# Multi_LT_circuit.net
KiCad netlist of a schematic drawn in Altium Designer
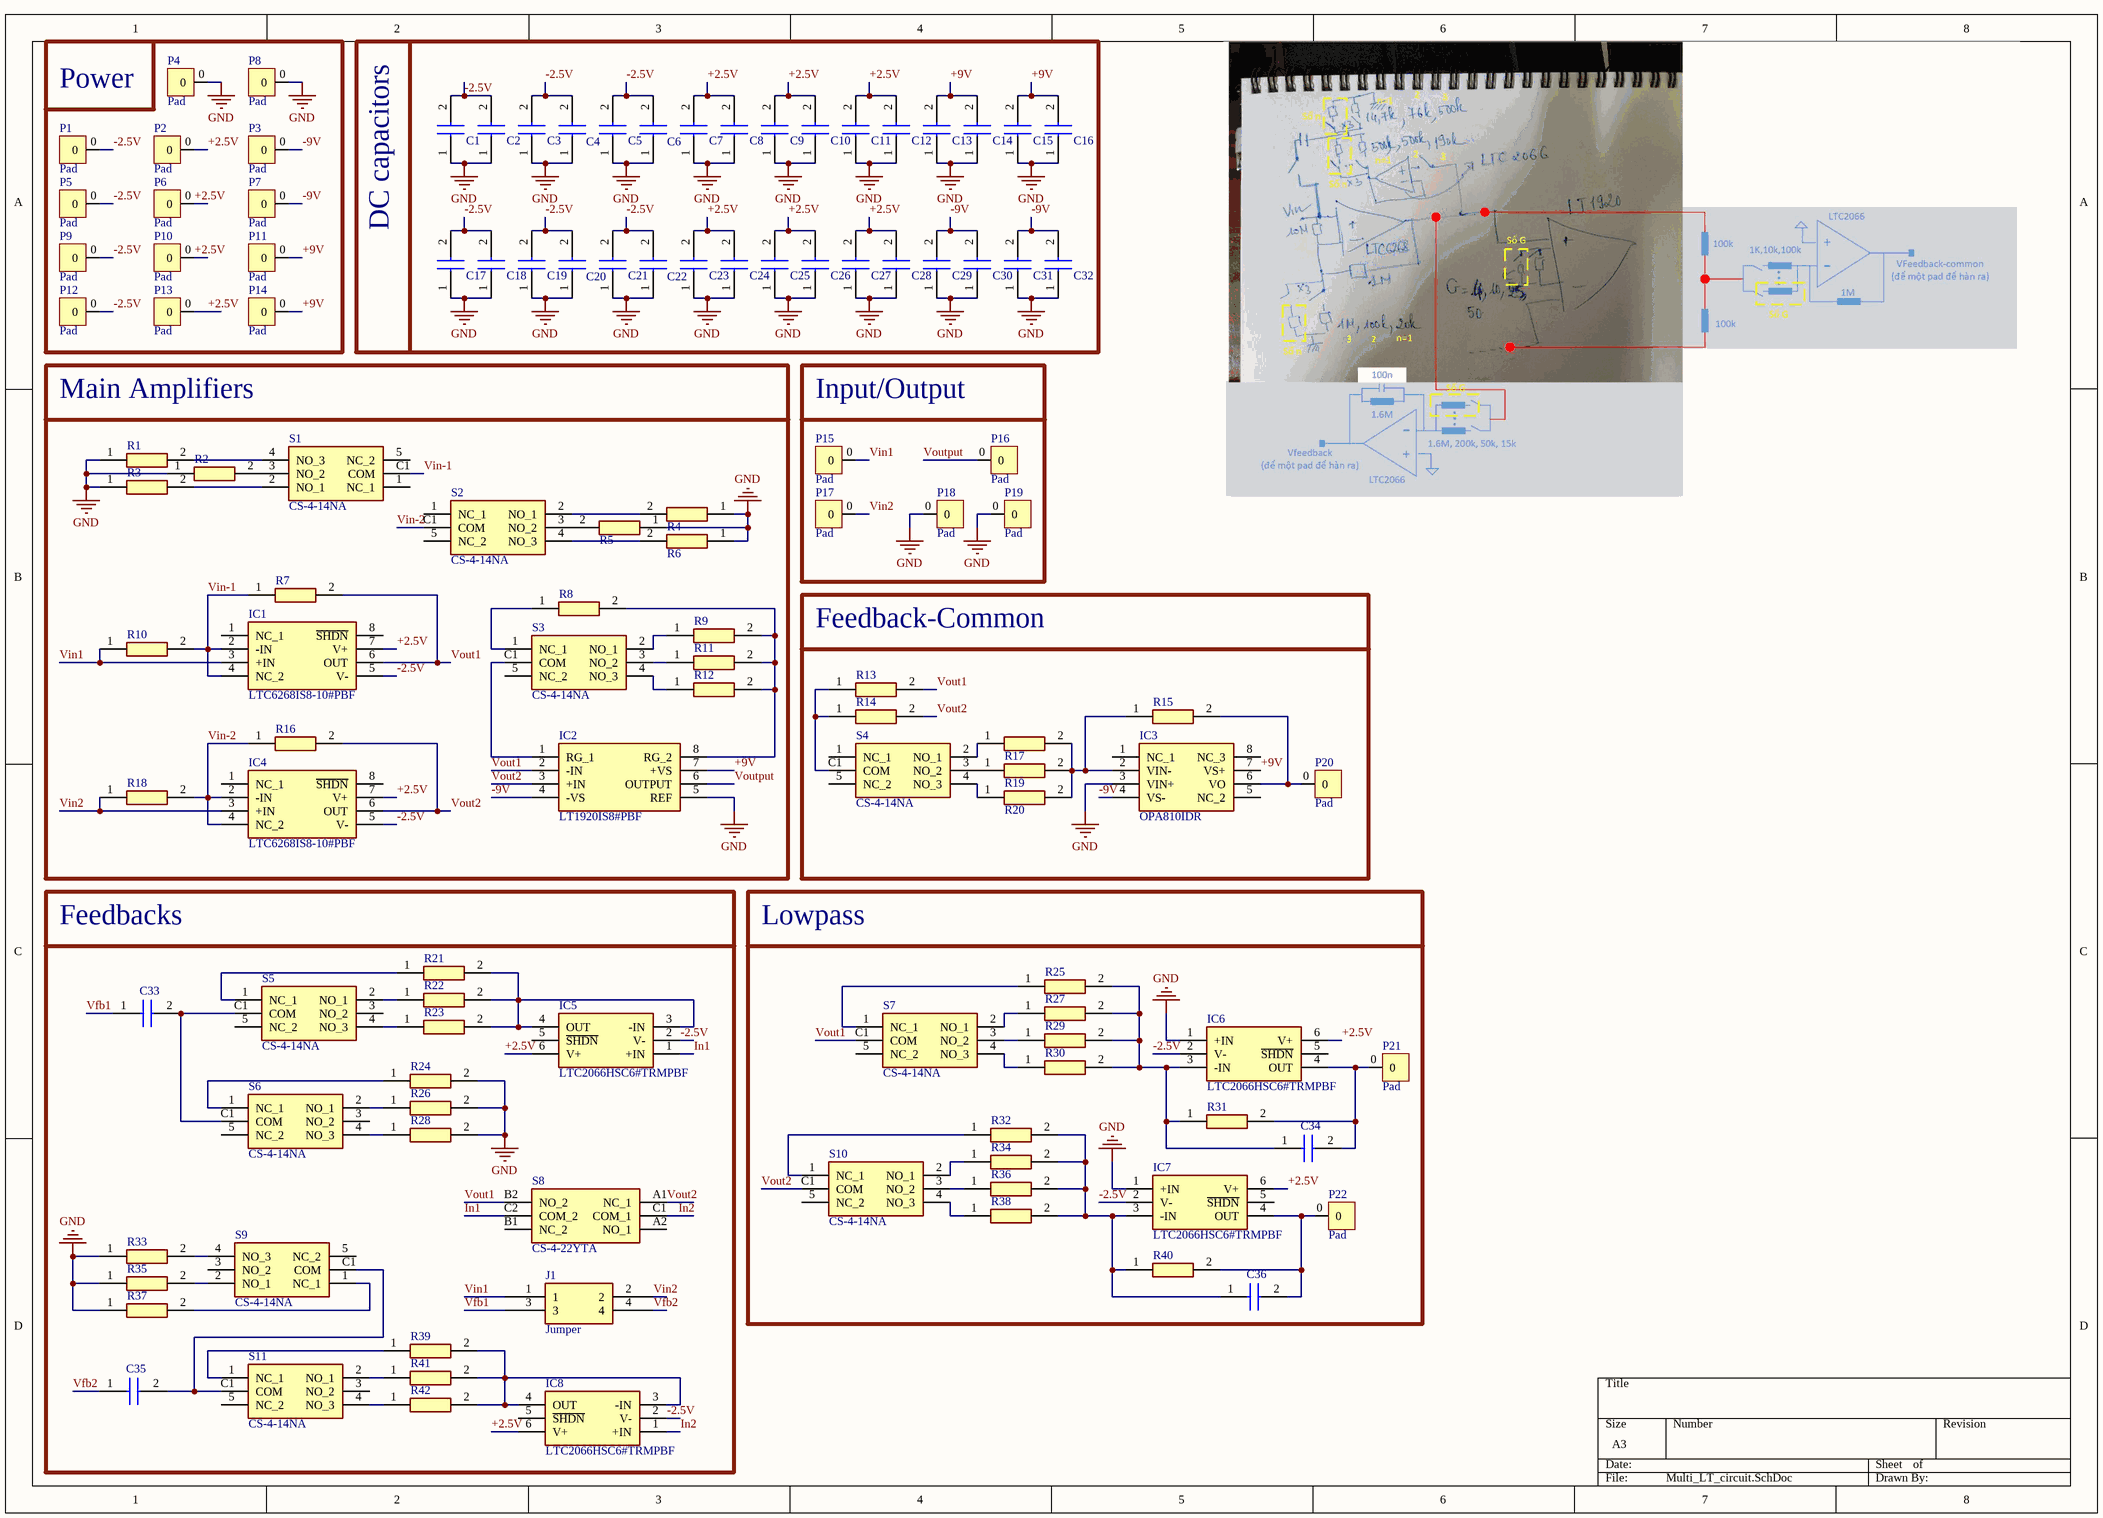
[diagram p0: Multi_LT_circuit.SchDoc]

(export (version "E")
  (design (tool "Eeschema 10.0.6"))
  (components
    (comp (ref "C1")
      (value "GCM21BD70J106KE02K")
      (footprint "SamacSys:CAPC2012X140N")
      (description "Capacitor 10uF")
      (fields (field (name "MOUSER PART NUMBER") "81-GCM21BD70J106KE2K"))
      (libsource (lib "SamacSys") (part "GCM21BD70J106KE02K"))
    )
    (comp (ref "C2")
      (value "GCJ21BR72A104KA01K")
      (footprint "SamacSys:CAPC2012X150N")
      (description "Capacitor 0.1uF")
      (fields (field (name "MOUSER PART NUMBER") "81-GCJ21BR72A104KA01"))
      (libsource (lib "SamacSys") (part "GCJ21BR72A104KA01K"))
    )
    (comp (ref "C3")
      (value "GCM21BD70J106KE02K")
      (footprint "SamacSys:CAPC2012X140N")
      (description "Capacitor 10uF")
      (fields (field (name "MOUSER PART NUMBER") "81-GCM21BD70J106KE2K"))
      (libsource (lib "SamacSys") (part "GCM21BD70J106KE02K"))
    )
    (comp (ref "C4")
      (value "GCJ21BR72A104KA01K")
      (footprint "SamacSys:CAPC2012X150N")
      (description "Capacitor 0.1uF")
      (fields (field (name "MOUSER PART NUMBER") "81-GCJ21BR72A104KA01"))
      (libsource (lib "SamacSys") (part "GCJ21BR72A104KA01K"))
    )
    (comp (ref "C5")
      (value "GCM21BD70J106KE02K")
      (footprint "SamacSys:CAPC2012X140N")
      (description "Capacitor 10uF")
      (fields (field (name "MOUSER PART NUMBER") "81-GCM21BD70J106KE2K"))
      (libsource (lib "SamacSys") (part "GCM21BD70J106KE02K"))
    )
    (comp (ref "C6")
      (value "GCJ21BR72A104KA01K")
      (footprint "SamacSys:CAPC2012X150N")
      (description "Capacitor 0.1uF")
      (fields (field (name "MOUSER PART NUMBER") "81-GCJ21BR72A104KA01"))
      (libsource (lib "SamacSys") (part "GCJ21BR72A104KA01K"))
    )
    (comp (ref "C7")
      (value "GCM21BD70J106KE02K")
      (footprint "SamacSys:CAPC2012X140N")
      (description "Capacitor 10uF")
      (fields (field (name "MOUSER PART NUMBER") "81-GCM21BD70J106KE2K"))
      (libsource (lib "SamacSys") (part "GCM21BD70J106KE02K"))
    )
    (comp (ref "C8")
      (value "GCJ21BR72A104KA01K")
      (footprint "SamacSys:CAPC2012X150N")
      (description "Capacitor 0.1uF")
      (fields (field (name "MOUSER PART NUMBER") "81-GCJ21BR72A104KA01"))
      (libsource (lib "SamacSys") (part "GCJ21BR72A104KA01K"))
    )
    (comp (ref "C9")
      (value "GCM21BD70J106KE02K")
      (footprint "SamacSys:CAPC2012X140N")
      (description "Capacitor 10uF")
      (fields (field (name "MOUSER PART NUMBER") "81-GCM21BD70J106KE2K"))
      (libsource (lib "SamacSys") (part "GCM21BD70J106KE02K"))
    )
    (comp (ref "C10")
      (value "GCJ21BR72A104KA01K")
      (footprint "SamacSys:CAPC2012X150N")
      (description "Capacitor 0.1uF")
      (fields (field (name "MOUSER PART NUMBER") "81-GCJ21BR72A104KA01"))
      (libsource (lib "SamacSys") (part "GCJ21BR72A104KA01K"))
    )
    (comp (ref "C11")
      (value "GCM21BD70J106KE02K")
      (footprint "SamacSys:CAPC2012X140N")
      (description "Capacitor 10uF")
      (fields (field (name "MOUSER PART NUMBER") "81-GCM21BD70J106KE2K"))
      (libsource (lib "SamacSys") (part "GCM21BD70J106KE02K"))
    )
    (comp (ref "C12")
      (value "GCJ21BR72A104KA01K")
      (footprint "SamacSys:CAPC2012X150N")
      (description "Capacitor 0.1uF")
      (fields (field (name "MOUSER PART NUMBER") "81-GCJ21BR72A104KA01"))
      (libsource (lib "SamacSys") (part "GCJ21BR72A104KA01K"))
    )
    (comp (ref "C13")
      (value "GCM21BD70J106KE02K")
      (footprint "SamacSys:CAPC2012X140N")
      (description "Capacitor 10uF")
      (fields (field (name "MOUSER PART NUMBER") "81-GCM21BD70J106KE2K"))
      (libsource (lib "SamacSys") (part "GCM21BD70J106KE02K"))
    )
    (comp (ref "C14")
      (value "GCJ21BR72A104KA01K")
      (footprint "SamacSys:CAPC2012X150N")
      (description "Capacitor 0.1uF")
      (fields (field (name "MOUSER PART NUMBER") "81-GCJ21BR72A104KA01"))
      (libsource (lib "SamacSys") (part "GCJ21BR72A104KA01K"))
    )
    (comp (ref "C15")
      (value "GCM21BD70J106KE02K")
      (footprint "SamacSys:CAPC2012X140N")
      (description "Capacitor 10uF")
      (fields (field (name "MOUSER PART NUMBER") "81-GCM21BD70J106KE2K"))
      (libsource (lib "SamacSys") (part "GCM21BD70J106KE02K"))
    )
    (comp (ref "C16")
      (value "GCJ21BR72A104KA01K")
      (footprint "SamacSys:CAPC2012X150N")
      (description "Capacitor 0.1uF")
      (fields (field (name "MOUSER PART NUMBER") "81-GCJ21BR72A104KA01"))
      (libsource (lib "SamacSys") (part "GCJ21BR72A104KA01K"))
    )
    (comp (ref "C17")
      (value "GCM21BD70J106KE02K")
      (footprint "SamacSys:CAPC2012X140N")
      (description "Capacitor 10uF")
      (fields (field (name "MOUSER PART NUMBER") "81-GCM21BD70J106KE2K"))
      (libsource (lib "SamacSys") (part "GCM21BD70J106KE02K"))
    )
    (comp (ref "C18")
      (value "GCJ21BR72A104KA01K")
      (footprint "SamacSys:CAPC2012X150N")
      (description "Capacitor 0.1uF")
      (fields (field (name "MOUSER PART NUMBER") "81-GCJ21BR72A104KA01"))
      (libsource (lib "SamacSys") (part "GCJ21BR72A104KA01K"))
    )
    (comp (ref "C19")
      (value "GCM21BD70J106KE02K")
      (footprint "SamacSys:CAPC2012X140N")
      (description "Capacitor 10uF")
      (fields (field (name "MOUSER PART NUMBER") "81-GCM21BD70J106KE2K"))
      (libsource (lib "SamacSys") (part "GCM21BD70J106KE02K"))
    )
    (comp (ref "C20")
      (value "GCJ21BR72A104KA01K")
      (footprint "SamacSys:CAPC2012X150N")
      (description "Capacitor 0.1uF")
      (fields (field (name "MOUSER PART NUMBER") "81-GCJ21BR72A104KA01"))
      (libsource (lib "SamacSys") (part "GCJ21BR72A104KA01K"))
    )
    (comp (ref "C21")
      (value "GCM21BD70J106KE02K")
      (footprint "SamacSys:CAPC2012X140N")
      (description "Capacitor 10uF")
      (fields (field (name "MOUSER PART NUMBER") "81-GCM21BD70J106KE2K"))
      (libsource (lib "SamacSys") (part "GCM21BD70J106KE02K"))
    )
    (comp (ref "C22")
      (value "GCJ21BR72A104KA01K")
      (footprint "SamacSys:CAPC2012X150N")
      (description "Capacitor 0.1uF")
      (fields (field (name "MOUSER PART NUMBER") "81-GCJ21BR72A104KA01"))
      (libsource (lib "SamacSys") (part "GCJ21BR72A104KA01K"))
    )
    (comp (ref "C23")
      (value "GCM21BD70J106KE02K")
      (footprint "SamacSys:CAPC2012X140N")
      (description "Capacitor 10uF")
      (fields (field (name "MOUSER PART NUMBER") "81-GCM21BD70J106KE2K"))
      (libsource (lib "SamacSys") (part "GCM21BD70J106KE02K"))
    )
    (comp (ref "C24")
      (value "GCJ21BR72A104KA01K")
      (footprint "SamacSys:CAPC2012X150N")
      (description "Capacitor 0.1uF")
      (fields (field (name "MOUSER PART NUMBER") "81-GCJ21BR72A104KA01"))
      (libsource (lib "SamacSys") (part "GCJ21BR72A104KA01K"))
    )
    (comp (ref "C25")
      (value "GCM21BD70J106KE02K")
      (footprint "SamacSys:CAPC2012X140N")
      (description "Capacitor 10uF")
      (fields (field (name "MOUSER PART NUMBER") "81-GCM21BD70J106KE2K"))
      (libsource (lib "SamacSys") (part "GCM21BD70J106KE02K"))
    )
    (comp (ref "C26")
      (value "GCJ21BR72A104KA01K")
      (footprint "SamacSys:CAPC2012X150N")
      (description "Capacitor 0.1uF")
      (fields (field (name "MOUSER PART NUMBER") "81-GCJ21BR72A104KA01"))
      (libsource (lib "SamacSys") (part "GCJ21BR72A104KA01K"))
    )
    (comp (ref "C27")
      (value "GCM21BD70J106KE02K")
      (footprint "SamacSys:CAPC2012X140N")
      (description "Capacitor 10uF")
      (fields (field (name "MOUSER PART NUMBER") "81-GCM21BD70J106KE2K"))
      (libsource (lib "SamacSys") (part "GCM21BD70J106KE02K"))
    )
    (comp (ref "C28")
      (value "GCJ21BR72A104KA01K")
      (footprint "SamacSys:CAPC2012X150N")
      (description "Capacitor 0.1uF")
      (fields (field (name "MOUSER PART NUMBER") "81-GCJ21BR72A104KA01"))
      (libsource (lib "SamacSys") (part "GCJ21BR72A104KA01K"))
    )
    (comp (ref "C29")
      (value "GCM21BD70J106KE02K")
      (footprint "SamacSys:CAPC2012X140N")
      (description "Capacitor 10uF")
      (fields (field (name "MOUSER PART NUMBER") "81-GCM21BD70J106KE2K"))
      (libsource (lib "SamacSys") (part "GCM21BD70J106KE02K"))
    )
    (comp (ref "C30")
      (value "GCJ21BR72A104KA01K")
      (footprint "SamacSys:CAPC2012X150N")
      (description "Capacitor 0.1uF")
      (fields (field (name "MOUSER PART NUMBER") "81-GCJ21BR72A104KA01"))
      (libsource (lib "SamacSys") (part "GCJ21BR72A104KA01K"))
    )
    (comp (ref "C31")
      (value "GCM21BD70J106KE02K")
      (footprint "SamacSys:CAPC2012X140N")
      (description "Capacitor 10uF")
      (fields (field (name "MOUSER PART NUMBER") "81-GCM21BD70J106KE2K"))
      (libsource (lib "SamacSys") (part "GCM21BD70J106KE02K"))
    )
    (comp (ref "C32")
      (value "GCJ21BR72A104KA01K")
      (footprint "SamacSys:CAPC2012X150N")
      (description "Capacitor 0.1uF")
      (fields (field (name "MOUSER PART NUMBER") "81-GCJ21BR72A104KA01"))
      (libsource (lib "SamacSys") (part "GCJ21BR72A104KA01K"))
    )
    (comp (ref "C33")
      (value "C0805C109B3GACTU")
      (footprint "SamacSys:C0805")
      (description "Capacitor 1pF")
      (libsource (lib "SamacSys") (part "C0805C109B3GACTU"))
    )
    (comp (ref "C34")
      (value "GCJ21BR72A104KA01K")
      (footprint "SamacSys:CAPC2012X150N")
      (description "Capacitor 0.1uF")
      (fields (field (name "MOUSER PART NUMBER") "81-GCJ21BR72A104KA01"))
      (libsource (lib "SamacSys") (part "GCJ21BR72A104KA01K"))
    )
    (comp (ref "C35")
      (value "C0805C109B3GACTU")
      (footprint "SamacSys:C0805")
      (description "Capacitor 1pF")
      (libsource (lib "SamacSys") (part "C0805C109B3GACTU"))
    )
    (comp (ref "C36")
      (value "GCJ21BR72A104KA01K")
      (footprint "SamacSys:CAPC2012X150N")
      (description "Capacitor 0.1uF")
      (fields (field (name "MOUSER PART NUMBER") "81-GCJ21BR72A104KA01"))
      (libsource (lib "SamacSys") (part "GCJ21BR72A104KA01K"))
    )
    (comp (ref "IC1")
      (value "LTC6268IS8-10#PBF")
      (footprint "SamacSys:SOIC127P599X175-8N")
      (description "Integrated Circuit")
      (fields (field (name "MOUSER PART NUMBER") "584-LTC6268IS8-10PBF"))
      (libsource (lib "SamacSys") (part "LTC6268IS8-10#PBF"))
    )
    (comp (ref "IC2")
      (value "LT1920IS8#PBF")
      (footprint "SamacSys:SOIC127P599X175-8N")
      (description "Integrated Circuit")
      (fields (field (name "MOUSER PART NUMBER") "584-LT1920IS8#PBF"))
      (libsource (lib "SamacSys") (part "LT1920IS8#PBF"))
    )
    (comp (ref "IC3")
      (value "OPA810IDR")
      (footprint "SamacSys:SOIC127P600X175-8N")
      (description "Integrated Circuit")
      (fields (field (name "MOUSER PART NUMBER") "595-OPA810IDR"))
      (libsource (lib "SamacSys") (part "OPA810IDR"))
    )
    (comp (ref "IC4")
      (value "LTC6268IS8-10#PBF")
      (footprint "SamacSys:SOIC127P599X175-8N")
      (description "Integrated Circuit")
      (fields (field (name "MOUSER PART NUMBER") "584-LTC6268IS8-10PBF"))
      (libsource (lib "SamacSys") (part "LTC6268IS8-10#PBF"))
    )
    (comp (ref "IC5")
      (value "LTC2066HSC6#TRMPBF")
      (footprint "SamacSys:SOT65P210X100-6N")
      (description "Integrated Circuit")
      (fields (field (name "MOUSER PART NUMBER") "584-LTC2066HSC6TRMPB"))
      (libsource (lib "") (part "LTC2066HSC6#TRMPBF_1"))
    )
    (comp (ref "IC6")
      (value "LTC2066HSC6#TRMPBF")
      (footprint "SamacSys:SOT65P210X100-6N")
      (description "Integrated Circuit")
      (fields (field (name "MOUSER PART NUMBER") "584-LTC2066HSC6TRMPB"))
      (libsource (lib "SamacSys") (part "LTC2066HSC6#TRMPBF"))
    )
    (comp (ref "IC7")
      (value "LTC2066HSC6#TRMPBF")
      (footprint "SamacSys:SOT65P210X100-6N")
      (description "Integrated Circuit")
      (fields (field (name "MOUSER PART NUMBER") "584-LTC2066HSC6TRMPB"))
      (libsource (lib "SamacSys") (part "LTC2066HSC6#TRMPBF"))
    )
    (comp (ref "IC8")
      (value "LTC2066HSC6#TRMPBF")
      (footprint "SamacSys:SOT65P210X100-6N")
      (description "Integrated Circuit")
      (fields (field (name "MOUSER PART NUMBER") "584-LTC2066HSC6TRMPB"))
      (libsource (lib "") (part "LTC2066HSC6#TRMPBF_1"))
    )
    (comp (ref "J1") (value "Jumper") (footprint "Jumper 2x2") (libsource (lib "SamacSys") (part "Jumper")))
    (comp (ref "P1") (value "Pad") (footprint "Pad") (libsource (lib "") (part "Pad_1")))
    (comp (ref "P2") (value "Pad") (footprint "Pad") (libsource (lib "") (part "Pad_1")))
    (comp (ref "P3") (value "Pad") (footprint "Pad") (libsource (lib "") (part "Pad_1")))
    (comp (ref "P4") (value "Pad") (footprint "Pad") (libsource (lib "") (part "Pad_1")))
    (comp (ref "P5") (value "Pad") (footprint "Pad") (libsource (lib "") (part "Pad_1")))
    (comp (ref "P6") (value "Pad") (footprint "Pad") (libsource (lib "") (part "Pad_1")))
    (comp (ref "P7") (value "Pad") (footprint "Pad") (libsource (lib "") (part "Pad_1")))
    (comp (ref "P8") (value "Pad") (footprint "Pad") (libsource (lib "") (part "Pad_1")))
    (comp (ref "P9") (value "Pad") (footprint "Pad") (libsource (lib "") (part "Pad_1")))
    (comp (ref "P10") (value "Pad") (footprint "Pad") (libsource (lib "") (part "Pad_1")))
    (comp (ref "P11") (value "Pad") (footprint "Pad") (libsource (lib "") (part "Pad_1")))
    (comp (ref "P12") (value "Pad") (footprint "Pad") (libsource (lib "") (part "Pad_1")))
    (comp (ref "P13") (value "Pad") (footprint "Pad") (libsource (lib "") (part "Pad_1")))
    (comp (ref "P14") (value "Pad") (footprint "Pad") (libsource (lib "") (part "Pad_1")))
    (comp (ref "P15") (value "Pad") (footprint "Pad") (libsource (lib "") (part "Pad_1")))
    (comp (ref "P16") (value "Pad") (footprint "Pad") (libsource (lib "SamacSys") (part "Pad")))
    (comp (ref "P17") (value "Pad") (footprint "Pad") (libsource (lib "") (part "Pad_1")))
    (comp (ref "P18") (value "Pad") (footprint "Pad") (libsource (lib "SamacSys") (part "Pad")))
    (comp (ref "P19") (value "Pad") (footprint "Pad") (libsource (lib "SamacSys") (part "Pad")))
    (comp (ref "P20") (value "Pad") (footprint "Pad") (libsource (lib "SamacSys") (part "Pad")))
    (comp (ref "P21") (value "Pad") (footprint "Pad") (libsource (lib "SamacSys") (part "Pad")))
    (comp (ref "P22") (value "Pad") (footprint "Pad") (libsource (lib "SamacSys") (part "Pad")))
    (comp (ref "R1")
      (value "CRG0805F20K")
      (footprint "SamacSys:RESC2012X65N")
      (description "Resistor 20k")
      (fields (field (name "MOUSER PART NUMBER") "279-CRG0805F20K"))
      (libsource (lib "") (part "CRG0805F20K_1"))
    )
    (comp (ref "R2")
      (value "CRG0805F100K")
      (footprint "SamacSys:RESC2012X65N")
      (description "Resistor 100k")
      (fields (field (name "MOUSER PART NUMBER") "279-CRG0805F100K"))
      (libsource (lib "SamacSys") (part "CRG0805F100K"))
    )
    (comp (ref "R3")
      (value "CRGH0805F1M0")
      (footprint "SamacSys:RESC2013X65N")
      (description "Resistor 1M")
      (fields (field (name "MOUSER PART NUMBER") "279-CRGH0805F1M0"))
      (libsource (lib "SamacSys") (part "CRGH0805F1M0"))
    )
    (comp (ref "R4")
      (value "CRG0805F20K")
      (footprint "SamacSys:RESC2012X65N")
      (description "Resistor 20k")
      (fields (field (name "MOUSER PART NUMBER") "279-CRG0805F20K"))
      (libsource (lib "SamacSys") (part "CRG0805F20K"))
    )
    (comp (ref "R5")
      (value "CRG0805F100K")
      (footprint "SamacSys:RESC2012X65N")
      (description "Resistor 100k")
      (fields (field (name "MOUSER PART NUMBER") "279-CRG0805F100K"))
      (libsource (lib "") (part "CRG0805F100K_1"))
    )
    (comp (ref "R6")
      (value "CRGH0805F1M0")
      (footprint "SamacSys:RESC2013X65N")
      (description "Resistor 1M")
      (fields (field (name "MOUSER PART NUMBER") "279-CRGH0805F1M0"))
      (libsource (lib "") (part "CRGH0805F1M0_1"))
    )
    (comp (ref "R7")
      (value "CRGH0805F1M0")
      (footprint "SamacSys:RESC2013X65N")
      (description "Resistor 1M")
      (fields (field (name "MOUSER PART NUMBER") "279-CRGH0805F1M0"))
      (libsource (lib "SamacSys") (part "CRGH0805F1M0"))
    )
    (comp (ref "R8")
      (value "CRGH0805F1K0")
      (footprint "SamacSys:RESC2013X65N")
      (description "Resistor 1k")
      (fields (field (name "MOUSER PART NUMBER") "279-CRGH0805F1K0"))
      (libsource (lib "SamacSys") (part "CRGH0805F1K0"))
    )
    (comp (ref "R9")
      (value "CRCW08052K05FKEA")
      (footprint "SamacSys:RESC2012X50N")
      (description "Resistor 2.05k")
      (fields (field (name "MOUSER PART NUMBER") "71-CRCW0805-2.05K-E3"))
      (libsource (lib "SamacSys") (part "CRCW08052K05FKEA"))
    )
    (comp (ref "R10")
      (value "CRGH0805J10M")
      (footprint "SamacSys:RESC2013X65N")
      (description "Resistor 10M")
      (fields (field (name "MOUSER PART NUMBER") "279-CRGH0805J10M"))
      (libsource (lib "SamacSys") (part "CRGH0805J10M"))
    )
    (comp (ref "R11")
      (value "CRCW08055K49FKEAHP")
      (footprint "SamacSys:RESC2012X60N")
      (description "Resistor 5.49k")
      (libsource (lib "SamacSys") (part "CRCW08055K49FKEAHP"))
    )
    (comp (ref "R12")
      (value "CRCW080516K5FKEA")
      (footprint "SamacSys:RESC2012X50N")
      (description "Resistor 16.5k")
      (fields (field (name "MOUSER PART NUMBER") "71-CRCW0805-16.5K-E3"))
      (libsource (lib "SamacSys") (part "CRCW080516K5FKEA"))
    )
    (comp (ref "R13")
      (value "CRG0805F100K")
      (footprint "SamacSys:RESC2012X65N")
      (description "Resistor 100k")
      (fields (field (name "MOUSER PART NUMBER") "279-CRG0805F100K"))
      (libsource (lib "SamacSys") (part "CRG0805F100K"))
    )
    (comp (ref "R14")
      (value "CRG0805F100K")
      (footprint "SamacSys:RESC2012X65N")
      (description "Resistor 100k")
      (fields (field (name "MOUSER PART NUMBER") "279-CRG0805F100K"))
      (libsource (lib "SamacSys") (part "CRG0805F100K"))
    )
    (comp (ref "R15")
      (value "CRGH0805F1M0")
      (footprint "SamacSys:RESC2013X65N")
      (description "Resistor 1M")
      (fields (field (name "MOUSER PART NUMBER") "279-CRGH0805F1M0"))
      (libsource (lib "SamacSys") (part "CRGH0805F1M0"))
    )
    (comp (ref "R16")
      (value "CRGH0805F1M0")
      (footprint "SamacSys:RESC2013X65N")
      (description "Resistor 1M")
      (fields (field (name "MOUSER PART NUMBER") "279-CRGH0805F1M0"))
      (libsource (lib "SamacSys") (part "CRGH0805F1M0"))
    )
    (comp (ref "R17")
      (value "CRG0805F100K")
      (footprint "SamacSys:RESC2012X65N")
      (description "Resistor 100k")
      (fields (field (name "MOUSER PART NUMBER") "279-CRG0805F100K"))
      (libsource (lib "SamacSys") (part "CRG0805F100K"))
    )
    (comp (ref "R18")
      (value "CRGH0805J10M")
      (footprint "SamacSys:RESC2013X65N")
      (description "Resistor 10M")
      (fields (field (name "MOUSER PART NUMBER") "279-CRGH0805J10M"))
      (libsource (lib "SamacSys") (part "CRGH0805J10M"))
    )
    (comp (ref "R19")
      (value "CRGH0805F10K")
      (footprint "SamacSys:RESC2013X65N")
      (description "Resistor 10k")
      (fields (field (name "MOUSER PART NUMBER") "279-CRGH0805F10K"))
      (libsource (lib "SamacSys") (part "CRGH0805F10K"))
    )
    (comp (ref "R20")
      (value "CRGH0805F1K0")
      (footprint "SamacSys:RESC2013X65N")
      (description "Resistor 1k")
      (fields (field (name "MOUSER PART NUMBER") "279-CRGH0805F1K0"))
      (libsource (lib "SamacSys") (part "CRGH0805F1K0"))
    )
    (comp (ref "R21")
      (value "CPF0805B499KE1")
      (footprint "SamacSys:RESC2012X65N")
      (description "Resistor 499k")
      (fields (field (name "MOUSER PART NUMBER") "279-CPF0805B499KE1"))
      (libsource (lib "SamacSys") (part "CPF0805B499KE1"))
    )
    (comp (ref "R22")
      (value "CPF0805B499KE1")
      (footprint "SamacSys:RESC2012X65N")
      (description "Resistor 499k")
      (fields (field (name "MOUSER PART NUMBER") "279-CPF0805B499KE1"))
      (libsource (lib "SamacSys") (part "CPF0805B499KE1"))
    )
    (comp (ref "R23")
      (value "CRGH0805F191K")
      (footprint "SamacSys:RESC2013X65N")
      (description "Resistor 191k")
      (fields (field (name "MOUSER PART NUMBER") "279-CRGH0805F191K"))
      (libsource (lib "SamacSys") (part "CRGH0805F191K"))
    )
    (comp (ref "R24")
      (value "CPF0805B499KE1")
      (footprint "SamacSys:RESC2012X65N")
      (description "Resistor 499k")
      (fields (field (name "MOUSER PART NUMBER") "279-CPF0805B499KE1"))
      (libsource (lib "SamacSys") (part "CPF0805B499KE1"))
    )
    (comp (ref "R25")
      (value "CPF0805B1M6E1")
      (footprint "SamacSys:RESC2012X65N")
      (description "Resistor 1.6M")
      (fields (field (name "MOUSER PART NUMBER") "279-CPF0805B1M6E1"))
      (libsource (lib "SamacSys") (part "CPF0805B1M6E1"))
    )
    (comp (ref "R26")
      (value "ERJ-6ENF7682V")
      (footprint "SamacSys:ERJ6ENF1000V")
      (description "Resistor 76.8k")
      (fields (field (name "MOUSER PART NUMBER") "667-ERJ-6ENF7682V"))
      (libsource (lib "SamacSys") (part "ERJ-6ENF7682V"))
    )
    (comp (ref "R27")
      (value "CPF-A-0805B200KE")
      (footprint "SamacSys:RESC2012X65N")
      (description "Resistor 200k")
      (fields (field (name "MOUSER PART NUMBER") "279-CPF-A-0805B200KE"))
      (libsource (lib "SamacSys") (part "CPF-A-0805B200KE"))
    )
    (comp (ref "R28")
      (value "CRCW080514K7FKEA")
      (footprint "SamacSys:RESC2012X50N")
      (description "Resistor 14.7k")
      (fields (field (name "MOUSER PART NUMBER") "71-CRCW0805-14.7K-E3"))
      (libsource (lib "SamacSys") (part "CRCW080514K7FKEA"))
    )
    (comp (ref "R29")
      (value "CPF-A-0805B49K9E1")
      (footprint "SamacSys:RESC2012X65N")
      (description "Resistor 49.9k")
      (fields (field (name "MOUSER PART NUMBER") "279-CPF-A0805B49K9E1"))
      (libsource (lib "SamacSys") (part "CPF-A-0805B49K9E1"))
    )
    (comp (ref "R30")
      (value "CRGH0805F15K")
      (footprint "SamacSys:RESC2013X65N")
      (description "Resistor 15k")
      (fields (field (name "MOUSER PART NUMBER") "279-CRGH0805F15K"))
      (libsource (lib "SamacSys") (part "CRGH0805F15K"))
    )
    (comp (ref "R31")
      (value "CPF0805B1M6E1")
      (footprint "SamacSys:RESC2012X65N")
      (description "Resistor 1.6M")
      (fields (field (name "MOUSER PART NUMBER") "279-CPF0805B1M6E1"))
      (libsource (lib "SamacSys") (part "CPF0805B1M6E1"))
    )
    (comp (ref "R32")
      (value "CPF0805B1M6E1")
      (footprint "SamacSys:RESC2012X65N")
      (description "Resistor 1.6M")
      (fields (field (name "MOUSER PART NUMBER") "279-CPF0805B1M6E1"))
      (libsource (lib "SamacSys") (part "CPF0805B1M6E1"))
    )
    (comp (ref "R33")
      (value "CRCW080514K7FKEA")
      (footprint "SamacSys:RESC2012X50N")
      (description "Resistor 14.7k")
      (fields (field (name "MOUSER PART NUMBER") "71-CRCW0805-14.7K-E3"))
      (libsource (lib "SamacSys") (part "CRCW080514K7FKEA"))
    )
    (comp (ref "R34")
      (value "CPF-A-0805B200KE")
      (footprint "SamacSys:RESC2012X65N")
      (description "Resistor 200k")
      (fields (field (name "MOUSER PART NUMBER") "279-CPF-A-0805B200KE"))
      (libsource (lib "SamacSys") (part "CPF-A-0805B200KE"))
    )
    (comp (ref "R35")
      (value "ERJ-6ENF7682V")
      (footprint "SamacSys:ERJ6ENF1000V")
      (description "Resistor 76.8k")
      (fields (field (name "MOUSER PART NUMBER") "667-ERJ-6ENF7682V"))
      (libsource (lib "SamacSys") (part "ERJ-6ENF7682V"))
    )
    (comp (ref "R36")
      (value "CPF-A-0805B49K9E1")
      (footprint "SamacSys:RESC2012X65N")
      (description "Resistor 49.9k")
      (fields (field (name "MOUSER PART NUMBER") "279-CPF-A0805B49K9E1"))
      (libsource (lib "SamacSys") (part "CPF-A-0805B49K9E1"))
    )
    (comp (ref "R37")
      (value "CPF0805B499KE1")
      (footprint "SamacSys:RESC2012X65N")
      (description "Resistor 499k")
      (fields (field (name "MOUSER PART NUMBER") "279-CPF0805B499KE1"))
      (libsource (lib "SamacSys") (part "CPF0805B499KE1"))
    )
    (comp (ref "R38")
      (value "CRGH0805F15K")
      (footprint "SamacSys:RESC2013X65N")
      (description "Resistor 15k")
      (fields (field (name "MOUSER PART NUMBER") "279-CRGH0805F15K"))
      (libsource (lib "SamacSys") (part "CRGH0805F15K"))
    )
    (comp (ref "R39")
      (value "CPF0805B499KE1")
      (footprint "SamacSys:RESC2012X65N")
      (description "Resistor 499k")
      (fields (field (name "MOUSER PART NUMBER") "279-CPF0805B499KE1"))
      (libsource (lib "SamacSys") (part "CPF0805B499KE1"))
    )
    (comp (ref "R40")
      (value "CPF0805B1M6E1")
      (footprint "SamacSys:RESC2012X65N")
      (description "Resistor 1.6M")
      (fields (field (name "MOUSER PART NUMBER") "279-CPF0805B1M6E1"))
      (libsource (lib "SamacSys") (part "CPF0805B1M6E1"))
    )
    (comp (ref "R41")
      (value "CPF0805B499KE1")
      (footprint "SamacSys:RESC2012X65N")
      (description "Resistor 499k")
      (fields (field (name "MOUSER PART NUMBER") "279-CPF0805B499KE1"))
      (libsource (lib "SamacSys") (part "CPF0805B499KE1"))
    )
    (comp (ref "R42")
      (value "CRGH0805F191K")
      (footprint "SamacSys:RESC2013X65N")
      (description "Resistor 191k")
      (fields (field (name "MOUSER PART NUMBER") "279-CRGH0805F191K"))
      (libsource (lib "SamacSys") (part "CRGH0805F191K"))
    )
    (comp (ref "S1")
      (value "CS-4-14NA")
      (footprint "SamacSys:CS414NA")
      (description "Switch")
      (fields (field (name "MOUSER PART NUMBER") "229-CS-4-14NA"))
      (libsource (lib "") (part "CS-4-14NA_1"))
    )
    (comp (ref "S2")
      (value "CS-4-14NA")
      (footprint "SamacSys:CS414NA")
      (description "Switch")
      (fields (field (name "MOUSER PART NUMBER") "229-CS-4-14NA"))
      (libsource (lib "SamacSys") (part "CS-4-14NA"))
    )
    (comp (ref "S3")
      (value "CS-4-14NA")
      (footprint "SamacSys:CS414NA")
      (description "Switch")
      (fields (field (name "MOUSER PART NUMBER") "229-CS-4-14NA"))
      (libsource (lib "SamacSys") (part "CS-4-14NA"))
    )
    (comp (ref "S4")
      (value "CS-4-14NA")
      (footprint "SamacSys:CS414NA")
      (description "Switch")
      (fields (field (name "MOUSER PART NUMBER") "229-CS-4-14NA"))
      (libsource (lib "SamacSys") (part "CS-4-14NA"))
    )
    (comp (ref "S5")
      (value "CS-4-14NA")
      (footprint "SamacSys:CS414NA")
      (description "Switch")
      (fields (field (name "MOUSER PART NUMBER") "229-CS-4-14NA"))
      (libsource (lib "SamacSys") (part "CS-4-14NA"))
    )
    (comp (ref "S6")
      (value "CS-4-14NA")
      (footprint "SamacSys:CS414NA")
      (description "Switch")
      (fields (field (name "MOUSER PART NUMBER") "229-CS-4-14NA"))
      (libsource (lib "SamacSys") (part "CS-4-14NA"))
    )
    (comp (ref "S7")
      (value "CS-4-14NA")
      (footprint "SamacSys:CS414NA")
      (description "Switch")
      (fields (field (name "MOUSER PART NUMBER") "229-CS-4-14NA"))
      (libsource (lib "SamacSys") (part "CS-4-14NA"))
    )
    (comp (ref "S8")
      (value "CS-4-22YTA")
      (footprint "SamacSys:CS422YTA")
      (description "Switch")
      (fields (field (name "MOUSER PART NUMBER") "229-CS-4-22YTA"))
      (libsource (lib "SamacSys") (part "CS-4-22YTA"))
    )
    (comp (ref "S9")
      (value "CS-4-14NA")
      (footprint "SamacSys:CS414NA")
      (description "Switch")
      (fields (field (name "MOUSER PART NUMBER") "229-CS-4-14NA"))
      (libsource (lib "") (part "CS-4-14NA_1"))
    )
    (comp (ref "S10")
      (value "CS-4-14NA")
      (footprint "SamacSys:CS414NA")
      (description "Switch")
      (fields (field (name "MOUSER PART NUMBER") "229-CS-4-14NA"))
      (libsource (lib "SamacSys") (part "CS-4-14NA"))
    )
    (comp (ref "S11")
      (value "CS-4-14NA")
      (footprint "SamacSys:CS414NA")
      (description "Switch")
      (fields (field (name "MOUSER PART NUMBER") "229-CS-4-14NA"))
      (libsource (lib "SamacSys") (part "CS-4-14NA"))
    )
  )
  (nets
    (net (code "1") (name "/+2.5V") (class "Default")
      (node (ref "C10") (pin "2") (pinfunction "2_2") (pintype "passive"))
      (node (ref "C11") (pin "2") (pinfunction "2_2") (pintype "passive"))
      (node (ref "C12") (pin "2") (pinfunction "2_2") (pintype "passive"))
      (node (ref "C23") (pin "2") (pinfunction "2_2") (pintype "passive"))
      (node (ref "C24") (pin "2") (pinfunction "2_2") (pintype "passive"))
      (node (ref "C25") (pin "2") (pinfunction "2_2") (pintype "passive"))
      (node (ref "C26") (pin "2") (pinfunction "2_2") (pintype "passive"))
      (node (ref "C27") (pin "2") (pinfunction "2_2") (pintype "passive"))
      (node (ref "C28") (pin "2") (pinfunction "2_2") (pintype "passive"))
      (node (ref "C7") (pin "2") (pinfunction "2_2") (pintype "passive"))
      (node (ref "C8") (pin "2") (pinfunction "2_2") (pintype "passive"))
      (node (ref "C9") (pin "2") (pinfunction "2_2") (pintype "passive"))
      (node (ref "IC1") (pin "7") (pinfunction "V+_7") (pintype "passive"))
      (node (ref "IC4") (pin "7") (pinfunction "V+_7") (pintype "passive"))
      (node (ref "IC5") (pin "6") (pinfunction "V+_6") (pintype "passive"))
      (node (ref "IC6") (pin "6") (pinfunction "V+_6") (pintype "passive"))
      (node (ref "IC7") (pin "6") (pinfunction "V+_6") (pintype "passive"))
      (node (ref "IC8") (pin "6") (pinfunction "V+_6") (pintype "passive"))
      (node (ref "P10") (pin "0") (pinfunction "0_0") (pintype "passive"))
      (node (ref "P13") (pin "0") (pinfunction "0_0") (pintype "passive"))
      (node (ref "P2") (pin "0") (pinfunction "0_0") (pintype "passive"))
      (node (ref "P6") (pin "0") (pinfunction "0_0") (pintype "passive"))
    )
    (net (code "2") (name "/+9V") (class "Default")
      (node (ref "C13") (pin "2") (pinfunction "2_2") (pintype "passive"))
      (node (ref "C14") (pin "2") (pinfunction "2_2") (pintype "passive"))
      (node (ref "C15") (pin "2") (pinfunction "2_2") (pintype "passive"))
      (node (ref "C16") (pin "2") (pinfunction "2_2") (pintype "passive"))
      (node (ref "IC2") (pin "7") (pinfunction "+VS_7") (pintype "passive"))
      (node (ref "IC3") (pin "7") (pinfunction "VS+_7") (pintype "passive"))
      (node (ref "P11") (pin "0") (pinfunction "0_0") (pintype "passive"))
      (node (ref "P14") (pin "0") (pinfunction "0_0") (pintype "passive"))
    )
    (net (code "3") (name "/-2.5V") (class "Default")
      (node (ref "C1") (pin "2") (pinfunction "2_2") (pintype "passive"))
      (node (ref "C17") (pin "2") (pinfunction "2_2") (pintype "passive"))
      (node (ref "C18") (pin "2") (pinfunction "2_2") (pintype "passive"))
      (node (ref "C19") (pin "2") (pinfunction "2_2") (pintype "passive"))
      (node (ref "C2") (pin "2") (pinfunction "2_2") (pintype "passive"))
      (node (ref "C20") (pin "2") (pinfunction "2_2") (pintype "passive"))
      (node (ref "C21") (pin "2") (pinfunction "2_2") (pintype "passive"))
      (node (ref "C22") (pin "2") (pinfunction "2_2") (pintype "passive"))
      (node (ref "C3") (pin "2") (pinfunction "2_2") (pintype "passive"))
      (node (ref "C4") (pin "2") (pinfunction "2_2") (pintype "passive"))
      (node (ref "C5") (pin "2") (pinfunction "2_2") (pintype "passive"))
      (node (ref "C6") (pin "2") (pinfunction "2_2") (pintype "passive"))
      (node (ref "IC1") (pin "5") (pinfunction "V-_5") (pintype "passive"))
      (node (ref "IC4") (pin "5") (pinfunction "V-_5") (pintype "passive"))
      (node (ref "IC5") (pin "2") (pinfunction "V-_2") (pintype "passive"))
      (node (ref "IC6") (pin "2") (pinfunction "V-_2") (pintype "passive"))
      (node (ref "IC7") (pin "2") (pinfunction "V-_2") (pintype "passive"))
      (node (ref "IC8") (pin "2") (pinfunction "V-_2") (pintype "passive"))
      (node (ref "P1") (pin "0") (pinfunction "0_0") (pintype "passive"))
      (node (ref "P12") (pin "0") (pinfunction "0_0") (pintype "passive"))
      (node (ref "P5") (pin "0") (pinfunction "0_0") (pintype "passive"))
      (node (ref "P9") (pin "0") (pinfunction "0_0") (pintype "passive"))
    )
    (net (code "4") (name "/-9V") (class "Default")
      (node (ref "C29") (pin "2") (pinfunction "2_2") (pintype "passive"))
      (node (ref "C30") (pin "2") (pinfunction "2_2") (pintype "passive"))
      (node (ref "C31") (pin "2") (pinfunction "2_2") (pintype "passive"))
      (node (ref "C32") (pin "2") (pinfunction "2_2") (pintype "passive"))
      (node (ref "IC2") (pin "4") (pinfunction "-VS_4") (pintype "passive"))
      (node (ref "IC3") (pin "4") (pinfunction "VS-_4") (pintype "passive"))
      (node (ref "P3") (pin "0") (pinfunction "0_0") (pintype "passive"))
      (node (ref "P7") (pin "0") (pinfunction "0_0") (pintype "passive"))
    )
    (net (code "5") (name "/In1") (class "Default")
      (node (ref "IC5") (pin "1") (pinfunction "+IN_1") (pintype "passive"))
      (node (ref "S8") (pin "C2") (pinfunction "COM_2_C2") (pintype "passive"))
    )
    (net (code "6") (name "/In2") (class "Default")
      (node (ref "IC8") (pin "1") (pinfunction "+IN_1") (pintype "passive"))
      (node (ref "S8") (pin "C1") (pinfunction "COM_1_C1") (pintype "passive"))
    )
    (net (code "7") (name "/Vfb1") (class "Default")
      (node (ref "C33") (pin "1") (pinfunction "1_1") (pintype "passive"))
      (node (ref "J1") (pin "3") (pinfunction "3_3") (pintype "passive"))
    )
    (net (code "8") (name "/Vfb2") (class "Default")
      (node (ref "C35") (pin "1") (pinfunction "1_1") (pintype "passive"))
      (node (ref "J1") (pin "4") (pinfunction "4_4") (pintype "passive"))
    )
    (net (code "9") (name "/Vin-1") (class "Default")
      (node (ref "IC1") (pin "2") (pinfunction "-IN_2") (pintype "passive"))
      (node (ref "IC1") (pin "4") (pinfunction "NC_2_4") (pintype "passive"))
      (node (ref "R10") (pin "2") (pinfunction "2_2") (pintype "passive"))
      (node (ref "R7") (pin "1") (pinfunction "1_1") (pintype "passive"))
      (node (ref "S1") (pin "C1") (pinfunction "COM_C1") (pintype "passive"))
    )
    (net (code "10") (name "/Vin-2") (class "Default")
      (node (ref "IC4") (pin "2") (pinfunction "-IN_2") (pintype "passive"))
      (node (ref "IC4") (pin "4") (pinfunction "NC_2_4") (pintype "passive"))
      (node (ref "R16") (pin "1") (pinfunction "1_1") (pintype "passive"))
      (node (ref "R18") (pin "2") (pinfunction "2_2") (pintype "passive"))
      (node (ref "S2") (pin "C1") (pinfunction "COM_C1") (pintype "passive"))
    )
    (net (code "11") (name "/Vin1") (class "Default")
      (node (ref "IC1") (pin "3") (pinfunction "+IN_3") (pintype "passive"))
      (node (ref "J1") (pin "1") (pinfunction "1_1") (pintype "passive"))
      (node (ref "P15") (pin "0") (pinfunction "0_0") (pintype "passive"))
      (node (ref "R10") (pin "1") (pinfunction "1_1") (pintype "passive"))
    )
    (net (code "12") (name "/Vin2") (class "Default")
      (node (ref "IC4") (pin "3") (pinfunction "+IN_3") (pintype "passive"))
      (node (ref "J1") (pin "2") (pinfunction "2_2") (pintype "passive"))
      (node (ref "P17") (pin "0") (pinfunction "0_0") (pintype "passive"))
      (node (ref "R18") (pin "1") (pinfunction "1_1") (pintype "passive"))
    )
    (net (code "13") (name "/Vout1") (class "Default")
      (node (ref "IC1") (pin "6") (pinfunction "OUT_6") (pintype "passive"))
      (node (ref "IC2") (pin "2") (pinfunction "-IN_2") (pintype "passive"))
      (node (ref "R13") (pin "2") (pinfunction "2_2") (pintype "passive"))
      (node (ref "R7") (pin "2") (pinfunction "2_2") (pintype "passive"))
      (node (ref "S7") (pin "C1") (pinfunction "COM_C1") (pintype "passive"))
      (node (ref "S8") (pin "B2") (pinfunction "NO_2_B2") (pintype "passive"))
    )
    (net (code "14") (name "/Vout2") (class "Default")
      (node (ref "IC2") (pin "3") (pinfunction "+IN_3") (pintype "passive"))
      (node (ref "IC4") (pin "6") (pinfunction "OUT_6") (pintype "passive"))
      (node (ref "R14") (pin "2") (pinfunction "2_2") (pintype "passive"))
      (node (ref "R16") (pin "2") (pinfunction "2_2") (pintype "passive"))
      (node (ref "S10") (pin "C1") (pinfunction "COM_C1") (pintype "passive"))
      (node (ref "S8") (pin "A1") (pinfunction "NC_1_A1") (pintype "passive"))
    )
    (net (code "15") (name "/Voutput") (class "Default")
      (node (ref "IC2") (pin "6") (pinfunction "OUTPUT_6") (pintype "passive"))
      (node (ref "P16") (pin "0") (pinfunction "0_0") (pintype "passive"))
    )
    (net (code "16") (name "GND") (class "Default")
      (node (ref "C1") (pin "1") (pinfunction "1_1") (pintype "passive"))
      (node (ref "C10") (pin "1") (pinfunction "1_1") (pintype "passive"))
      (node (ref "C11") (pin "1") (pinfunction "1_1") (pintype "passive"))
      (node (ref "C12") (pin "1") (pinfunction "1_1") (pintype "passive"))
      (node (ref "C13") (pin "1") (pinfunction "1_1") (pintype "passive"))
      (node (ref "C14") (pin "1") (pinfunction "1_1") (pintype "passive"))
      (node (ref "C15") (pin "1") (pinfunction "1_1") (pintype "passive"))
      (node (ref "C16") (pin "1") (pinfunction "1_1") (pintype "passive"))
      (node (ref "C17") (pin "1") (pinfunction "1_1") (pintype "passive"))
      (node (ref "C18") (pin "1") (pinfunction "1_1") (pintype "passive"))
      (node (ref "C19") (pin "1") (pinfunction "1_1") (pintype "passive"))
      (node (ref "C2") (pin "1") (pinfunction "1_1") (pintype "passive"))
      (node (ref "C20") (pin "1") (pinfunction "1_1") (pintype "passive"))
      (node (ref "C21") (pin "1") (pinfunction "1_1") (pintype "passive"))
      (node (ref "C22") (pin "1") (pinfunction "1_1") (pintype "passive"))
      (node (ref "C23") (pin "1") (pinfunction "1_1") (pintype "passive"))
      (node (ref "C24") (pin "1") (pinfunction "1_1") (pintype "passive"))
      (node (ref "C25") (pin "1") (pinfunction "1_1") (pintype "passive"))
      (node (ref "C26") (pin "1") (pinfunction "1_1") (pintype "passive"))
      (node (ref "C27") (pin "1") (pinfunction "1_1") (pintype "passive"))
      (node (ref "C28") (pin "1") (pinfunction "1_1") (pintype "passive"))
      (node (ref "C29") (pin "1") (pinfunction "1_1") (pintype "passive"))
      (node (ref "C3") (pin "1") (pinfunction "1_1") (pintype "passive"))
      (node (ref "C30") (pin "1") (pinfunction "1_1") (pintype "passive"))
      (node (ref "C31") (pin "1") (pinfunction "1_1") (pintype "passive"))
      (node (ref "C32") (pin "1") (pinfunction "1_1") (pintype "passive"))
      (node (ref "C4") (pin "1") (pinfunction "1_1") (pintype "passive"))
      (node (ref "C5") (pin "1") (pinfunction "1_1") (pintype "passive"))
      (node (ref "C6") (pin "1") (pinfunction "1_1") (pintype "passive"))
      (node (ref "C7") (pin "1") (pinfunction "1_1") (pintype "passive"))
      (node (ref "C8") (pin "1") (pinfunction "1_1") (pintype "passive"))
      (node (ref "C9") (pin "1") (pinfunction "1_1") (pintype "passive"))
      (node (ref "IC2") (pin "5") (pinfunction "REF_5") (pintype "passive"))
      (node (ref "IC3") (pin "3") (pinfunction "VIN+_3") (pintype "passive"))
      (node (ref "IC6") (pin "1") (pinfunction "+IN_1") (pintype "passive"))
      (node (ref "IC7") (pin "1") (pinfunction "+IN_1") (pintype "passive"))
      (node (ref "P18") (pin "0") (pinfunction "0_0") (pintype "passive"))
      (node (ref "P19") (pin "0") (pinfunction "0_0") (pintype "passive"))
      (node (ref "P4") (pin "0") (pinfunction "0_0") (pintype "passive"))
      (node (ref "P8") (pin "0") (pinfunction "0_0") (pintype "passive"))
      (node (ref "R1") (pin "1") (pinfunction "1_1") (pintype "passive"))
      (node (ref "R2") (pin "1") (pinfunction "1_1") (pintype "passive"))
      (node (ref "R24") (pin "2") (pinfunction "2_2") (pintype "passive"))
      (node (ref "R26") (pin "2") (pinfunction "2_2") (pintype "passive"))
      (node (ref "R28") (pin "2") (pinfunction "2_2") (pintype "passive"))
      (node (ref "R3") (pin "1") (pinfunction "1_1") (pintype "passive"))
      (node (ref "R33") (pin "1") (pinfunction "1_1") (pintype "passive"))
      (node (ref "R35") (pin "1") (pinfunction "1_1") (pintype "passive"))
      (node (ref "R37") (pin "1") (pinfunction "1_1") (pintype "passive"))
      (node (ref "R4") (pin "1") (pinfunction "1_1") (pintype "passive"))
      (node (ref "R5") (pin "1") (pinfunction "1_1") (pintype "passive"))
      (node (ref "R6") (pin "1") (pinfunction "1_1") (pintype "passive"))
    )
    (net (code "17") (name "Net-(IC2-RG_1)") (class "Default")
      (node (ref "IC2") (pin "1") (pinfunction "RG_1_1") (pintype "passive"))
      (node (ref "S3") (pin "C1") (pinfunction "COM_C1") (pintype "passive"))
    )
    (net (code "18") (name "Net-(IC2-RG_2)") (class "Default")
      (node (ref "IC2") (pin "8") (pinfunction "RG_2_8") (pintype "passive"))
      (node (ref "R11") (pin "2") (pinfunction "2_2") (pintype "passive"))
      (node (ref "R12") (pin "2") (pinfunction "2_2") (pintype "passive"))
      (node (ref "R8") (pin "2") (pinfunction "2_2") (pintype "passive"))
      (node (ref "R9") (pin "2") (pinfunction "2_2") (pintype "passive"))
    )
    (net (code "19") (name "Net-(IC3-VIN-)") (class "Default")
      (node (ref "IC3") (pin "2") (pinfunction "VIN-_2") (pintype "passive"))
      (node (ref "R15") (pin "1") (pinfunction "1_1") (pintype "passive"))
      (node (ref "R17") (pin "2") (pinfunction "2_2") (pintype "passive"))
      (node (ref "R19") (pin "2") (pinfunction "2_2") (pintype "passive"))
      (node (ref "R20") (pin "2") (pinfunction "2_2") (pintype "passive"))
    )
    (net (code "20") (name "Net-(IC3-VO)") (class "Default")
      (node (ref "IC3") (pin "6") (pinfunction "VO_6") (pintype "passive"))
      (node (ref "P20") (pin "0") (pinfunction "0_0") (pintype "passive"))
      (node (ref "R15") (pin "2") (pinfunction "2_2") (pintype "passive"))
    )
    (net (code "21") (name "Net-(IC5--IN)") (class "Default")
      (node (ref "IC5") (pin "3") (pinfunction "-IN_3") (pintype "passive"))
      (node (ref "IC5") (pin "4") (pinfunction "OUT_4") (pintype "passive"))
      (node (ref "R21") (pin "2") (pinfunction "2_2") (pintype "passive"))
      (node (ref "R22") (pin "2") (pinfunction "2_2") (pintype "passive"))
      (node (ref "R23") (pin "2") (pinfunction "2_2") (pintype "passive"))
    )
    (net (code "22") (name "Net-(IC6--IN)") (class "Default")
      (node (ref "C34") (pin "1") (pinfunction "1_1") (pintype "passive"))
      (node (ref "IC6") (pin "3") (pinfunction "-IN_3") (pintype "passive"))
      (node (ref "R25") (pin "2") (pinfunction "2_2") (pintype "passive"))
      (node (ref "R27") (pin "2") (pinfunction "2_2") (pintype "passive"))
      (node (ref "R29") (pin "2") (pinfunction "2_2") (pintype "passive"))
      (node (ref "R30") (pin "2") (pinfunction "2_2") (pintype "passive"))
      (node (ref "R31") (pin "1") (pinfunction "1_1") (pintype "passive"))
    )
    (net (code "23") (name "Net-(IC6-OUT)") (class "Default")
      (node (ref "C34") (pin "2") (pinfunction "2_2") (pintype "passive"))
      (node (ref "IC6") (pin "4") (pinfunction "OUT_4") (pintype "passive"))
      (node (ref "P21") (pin "0") (pinfunction "0_0") (pintype "passive"))
      (node (ref "R31") (pin "2") (pinfunction "2_2") (pintype "passive"))
    )
    (net (code "24") (name "Net-(IC7--IN)") (class "Default")
      (node (ref "C36") (pin "1") (pinfunction "1_1") (pintype "passive"))
      (node (ref "IC7") (pin "3") (pinfunction "-IN_3") (pintype "passive"))
      (node (ref "R32") (pin "2") (pinfunction "2_2") (pintype "passive"))
      (node (ref "R34") (pin "2") (pinfunction "2_2") (pintype "passive"))
      (node (ref "R36") (pin "2") (pinfunction "2_2") (pintype "passive"))
      (node (ref "R38") (pin "2") (pinfunction "2_2") (pintype "passive"))
      (node (ref "R40") (pin "1") (pinfunction "1_1") (pintype "passive"))
    )
    (net (code "25") (name "Net-(IC7-OUT)") (class "Default")
      (node (ref "C36") (pin "2") (pinfunction "2_2") (pintype "passive"))
      (node (ref "IC7") (pin "4") (pinfunction "OUT_4") (pintype "passive"))
      (node (ref "P22") (pin "0") (pinfunction "0_0") (pintype "passive"))
      (node (ref "R40") (pin "2") (pinfunction "2_2") (pintype "passive"))
    )
    (net (code "26") (name "Net-(IC8--IN)") (class "Default")
      (node (ref "IC8") (pin "3") (pinfunction "-IN_3") (pintype "passive"))
      (node (ref "IC8") (pin "4") (pinfunction "OUT_4") (pintype "passive"))
      (node (ref "R39") (pin "2") (pinfunction "2_2") (pintype "passive"))
      (node (ref "R41") (pin "2") (pinfunction "2_2") (pintype "passive"))
      (node (ref "R42") (pin "2") (pinfunction "2_2") (pintype "passive"))
    )
    (net (code "27") (name "Net-(S1-NO_1)") (class "Default")
      (node (ref "R3") (pin "2") (pinfunction "2_2") (pintype "passive"))
      (node (ref "S1") (pin "2") (pinfunction "NO_1_2") (pintype "passive"))
    )
    (net (code "28") (name "Net-(S1-NO_2)") (class "Default")
      (node (ref "R2") (pin "2") (pinfunction "2_2") (pintype "passive"))
      (node (ref "S1") (pin "3") (pinfunction "NO_2_3") (pintype "passive"))
    )
    (net (code "29") (name "Net-(S1-NO_3)") (class "Default")
      (node (ref "R1") (pin "2") (pinfunction "2_2") (pintype "passive"))
      (node (ref "S1") (pin "4") (pinfunction "NO_3_4") (pintype "passive"))
    )
    (net (code "30") (name "Net-(S2-NO_1)") (class "Default")
      (node (ref "R4") (pin "2") (pinfunction "2_2") (pintype "passive"))
      (node (ref "S2") (pin "2") (pinfunction "NO_1_2") (pintype "passive"))
    )
    (net (code "31") (name "Net-(S2-NO_2)") (class "Default")
      (node (ref "R5") (pin "2") (pinfunction "2_2") (pintype "passive"))
      (node (ref "S2") (pin "3") (pinfunction "NO_2_3") (pintype "passive"))
    )
    (net (code "32") (name "Net-(S2-NO_3)") (class "Default")
      (node (ref "R6") (pin "2") (pinfunction "2_2") (pintype "passive"))
      (node (ref "S2") (pin "4") (pinfunction "NO_3_4") (pintype "passive"))
    )
    (net (code "33") (name "Net-(S3-NC_1)") (class "Default")
      (node (ref "R8") (pin "1") (pinfunction "1_1") (pintype "passive"))
      (node (ref "S3") (pin "1") (pinfunction "NC_1_1") (pintype "passive"))
    )
    (net (code "34") (name "Net-(S3-NO_1)") (class "Default")
      (node (ref "R9") (pin "1") (pinfunction "1_1") (pintype "passive"))
      (node (ref "S3") (pin "2") (pinfunction "NO_1_2") (pintype "passive"))
    )
    (net (code "35") (name "Net-(S3-NO_2)") (class "Default")
      (node (ref "R11") (pin "1") (pinfunction "1_1") (pintype "passive"))
      (node (ref "S3") (pin "3") (pinfunction "NO_2_3") (pintype "passive"))
    )
    (net (code "36") (name "Net-(S3-NO_3)") (class "Default")
      (node (ref "R12") (pin "1") (pinfunction "1_1") (pintype "passive"))
      (node (ref "S3") (pin "4") (pinfunction "NO_3_4") (pintype "passive"))
    )
    (net (code "37") (name "Net-(S4-COM)") (class "Default")
      (node (ref "R13") (pin "1") (pinfunction "1_1") (pintype "passive"))
      (node (ref "R14") (pin "1") (pinfunction "1_1") (pintype "passive"))
      (node (ref "S4") (pin "C1") (pinfunction "COM_C1") (pintype "passive"))
    )
    (net (code "38") (name "Net-(S4-NO_1)") (class "Default")
      (node (ref "R17") (pin "1") (pinfunction "1_1") (pintype "passive"))
      (node (ref "S4") (pin "2") (pinfunction "NO_1_2") (pintype "passive"))
    )
    (net (code "39") (name "Net-(S4-NO_2)") (class "Default")
      (node (ref "R19") (pin "1") (pinfunction "1_1") (pintype "passive"))
      (node (ref "S4") (pin "3") (pinfunction "NO_2_3") (pintype "passive"))
    )
    (net (code "40") (name "Net-(S4-NO_3)") (class "Default")
      (node (ref "R20") (pin "1") (pinfunction "1_1") (pintype "passive"))
      (node (ref "S4") (pin "4") (pinfunction "NO_3_4") (pintype "passive"))
    )
    (net (code "41") (name "Net-(S5-COM)") (class "Default")
      (node (ref "C33") (pin "2") (pinfunction "2_2") (pintype "passive"))
      (node (ref "S5") (pin "C1") (pinfunction "COM_C1") (pintype "passive"))
      (node (ref "S6") (pin "C1") (pinfunction "COM_C1") (pintype "passive"))
    )
    (net (code "42") (name "Net-(S5-NC_1)") (class "Default")
      (node (ref "R21") (pin "1") (pinfunction "1_1") (pintype "passive"))
      (node (ref "S5") (pin "1") (pinfunction "NC_1_1") (pintype "passive"))
    )
    (net (code "43") (name "Net-(S5-NO_1)") (class "Default")
      (node (ref "R22") (pin "1") (pinfunction "1_1") (pintype "passive"))
      (node (ref "S5") (pin "2") (pinfunction "NO_1_2") (pintype "passive"))
    )
    (net (code "44") (name "Net-(S5-NO_3)") (class "Default")
      (node (ref "R23") (pin "1") (pinfunction "1_1") (pintype "passive"))
      (node (ref "S5") (pin "4") (pinfunction "NO_3_4") (pintype "passive"))
    )
    (net (code "45") (name "Net-(S6-NC_1)") (class "Default")
      (node (ref "R24") (pin "1") (pinfunction "1_1") (pintype "passive"))
      (node (ref "S6") (pin "1") (pinfunction "NC_1_1") (pintype "passive"))
    )
    (net (code "46") (name "Net-(S6-NO_1)") (class "Default")
      (node (ref "R26") (pin "1") (pinfunction "1_1") (pintype "passive"))
      (node (ref "S6") (pin "2") (pinfunction "NO_1_2") (pintype "passive"))
    )
    (net (code "47") (name "Net-(S6-NO_3)") (class "Default")
      (node (ref "R28") (pin "1") (pinfunction "1_1") (pintype "passive"))
      (node (ref "S6") (pin "4") (pinfunction "NO_3_4") (pintype "passive"))
    )
    (net (code "48") (name "Net-(S7-NC_1)") (class "Default")
      (node (ref "R25") (pin "1") (pinfunction "1_1") (pintype "passive"))
      (node (ref "S7") (pin "1") (pinfunction "NC_1_1") (pintype "passive"))
    )
    (net (code "49") (name "Net-(S7-NO_1)") (class "Default")
      (node (ref "R27") (pin "1") (pinfunction "1_1") (pintype "passive"))
      (node (ref "S7") (pin "2") (pinfunction "NO_1_2") (pintype "passive"))
    )
    (net (code "50") (name "Net-(S7-NO_2)") (class "Default")
      (node (ref "R29") (pin "1") (pinfunction "1_1") (pintype "passive"))
      (node (ref "S7") (pin "3") (pinfunction "NO_2_3") (pintype "passive"))
    )
    (net (code "51") (name "Net-(S7-NO_3)") (class "Default")
      (node (ref "R30") (pin "1") (pinfunction "1_1") (pintype "passive"))
      (node (ref "S7") (pin "4") (pinfunction "NO_3_4") (pintype "passive"))
    )
    (net (code "52") (name "Net-(S9-NC_1)") (class "Default")
      (node (ref "R37") (pin "2") (pinfunction "2_2") (pintype "passive"))
      (node (ref "S9") (pin "1") (pinfunction "NC_1_1") (pintype "passive"))
    )
    (net (code "53") (name "Net-(S9-NO_1)") (class "Default")
      (node (ref "R35") (pin "2") (pinfunction "2_2") (pintype "passive"))
      (node (ref "S9") (pin "2") (pinfunction "NO_1_2") (pintype "passive"))
    )
    (net (code "54") (name "Net-(S9-NO_3)") (class "Default")
      (node (ref "R33") (pin "2") (pinfunction "2_2") (pintype "passive"))
      (node (ref "S9") (pin "4") (pinfunction "NO_3_4") (pintype "passive"))
    )
    (net (code "55") (name "Net-(S10-NC_1)") (class "Default")
      (node (ref "R32") (pin "1") (pinfunction "1_1") (pintype "passive"))
      (node (ref "S10") (pin "1") (pinfunction "NC_1_1") (pintype "passive"))
    )
    (net (code "56") (name "Net-(S10-NO_1)") (class "Default")
      (node (ref "R34") (pin "1") (pinfunction "1_1") (pintype "passive"))
      (node (ref "S10") (pin "2") (pinfunction "NO_1_2") (pintype "passive"))
    )
    (net (code "57") (name "Net-(S10-NO_2)") (class "Default")
      (node (ref "R36") (pin "1") (pinfunction "1_1") (pintype "passive"))
      (node (ref "S10") (pin "3") (pinfunction "NO_2_3") (pintype "passive"))
    )
    (net (code "58") (name "Net-(S10-NO_3)") (class "Default")
      (node (ref "R38") (pin "1") (pinfunction "1_1") (pintype "passive"))
      (node (ref "S10") (pin "4") (pinfunction "NO_3_4") (pintype "passive"))
    )
    (net (code "59") (name "Net-(S11-COM)") (class "Default")
      (node (ref "C35") (pin "2") (pinfunction "2_2") (pintype "passive"))
      (node (ref "S11") (pin "C1") (pinfunction "COM_C1") (pintype "passive"))
      (node (ref "S9") (pin "C1") (pinfunction "COM_C1") (pintype "passive"))
    )
    (net (code "60") (name "Net-(S11-NC_1)") (class "Default")
      (node (ref "R39") (pin "1") (pinfunction "1_1") (pintype "passive"))
      (node (ref "S11") (pin "1") (pinfunction "NC_1_1") (pintype "passive"))
    )
    (net (code "61") (name "Net-(S11-NO_1)") (class "Default")
      (node (ref "R41") (pin "1") (pinfunction "1_1") (pintype "passive"))
      (node (ref "S11") (pin "2") (pinfunction "NO_1_2") (pintype "passive"))
    )
    (net (code "62") (name "Net-(S11-NO_3)") (class "Default")
      (node (ref "R42") (pin "1") (pinfunction "1_1") (pintype "passive"))
      (node (ref "S11") (pin "4") (pinfunction "NO_3_4") (pintype "passive"))
    )
    (net (code "63") (name "unconnected-(IC1-NC_1-Pad1)") (class "Default")
      (node (ref "IC1") (pin "1") (pinfunction "NC_1_1") (pintype "passive"))
    )
    (net (code "64") (name "unconnected-(IC1-~{SHDN}-Pad8)") (class "Default")
      (node (ref "IC1") (pin "8") (pinfunction "~{SHDN}_8") (pintype "passive"))
    )
    (net (code "65") (name "unconnected-(IC3-NC_1-Pad1)") (class "Default")
      (node (ref "IC3") (pin "1") (pinfunction "NC_1_1") (pintype "passive"))
    )
    (net (code "66") (name "unconnected-(IC3-NC_2-Pad5)") (class "Default")
      (node (ref "IC3") (pin "5") (pinfunction "NC_2_5") (pintype "passive"))
    )
    (net (code "67") (name "unconnected-(IC3-NC_3-Pad8)") (class "Default")
      (node (ref "IC3") (pin "8") (pinfunction "NC_3_8") (pintype "passive"))
    )
    (net (code "68") (name "unconnected-(IC4-NC_1-Pad1)") (class "Default")
      (node (ref "IC4") (pin "1") (pinfunction "NC_1_1") (pintype "passive"))
    )
    (net (code "69") (name "unconnected-(IC4-~{SHDN}-Pad8)") (class "Default")
      (node (ref "IC4") (pin "8") (pinfunction "~{SHDN}_8") (pintype "passive"))
    )
    (net (code "70") (name "unconnected-(IC5-~{SHDN}-Pad5)") (class "Default")
      (node (ref "IC5") (pin "5") (pinfunction "~{SHDN}_5") (pintype "passive"))
    )
    (net (code "71") (name "unconnected-(IC6-~{SHDN}-Pad5)") (class "Default")
      (node (ref "IC6") (pin "5") (pinfunction "~{SHDN}_5") (pintype "passive"))
    )
    (net (code "72") (name "unconnected-(IC7-~{SHDN}-Pad5)") (class "Default")
      (node (ref "IC7") (pin "5") (pinfunction "~{SHDN}_5") (pintype "passive"))
    )
    (net (code "73") (name "unconnected-(IC8-~{SHDN}-Pad5)") (class "Default")
      (node (ref "IC8") (pin "5") (pinfunction "~{SHDN}_5") (pintype "passive"))
    )
    (net (code "74") (name "unconnected-(S1-NC_1-Pad1)") (class "Default")
      (node (ref "S1") (pin "1") (pinfunction "NC_1_1") (pintype "passive"))
    )
    (net (code "75") (name "unconnected-(S1-NC_2-Pad5)") (class "Default")
      (node (ref "S1") (pin "5") (pinfunction "NC_2_5") (pintype "passive"))
    )
    (net (code "76") (name "unconnected-(S2-NC_1-Pad1)") (class "Default")
      (node (ref "S2") (pin "1") (pinfunction "NC_1_1") (pintype "passive"))
    )
    (net (code "77") (name "unconnected-(S2-NC_2-Pad5)") (class "Default")
      (node (ref "S2") (pin "5") (pinfunction "NC_2_5") (pintype "passive"))
    )
    (net (code "78") (name "unconnected-(S3-NC_2-Pad5)") (class "Default")
      (node (ref "S3") (pin "5") (pinfunction "NC_2_5") (pintype "passive"))
    )
    (net (code "79") (name "unconnected-(S4-NC_1-Pad1)") (class "Default")
      (node (ref "S4") (pin "1") (pinfunction "NC_1_1") (pintype "passive"))
    )
    (net (code "80") (name "unconnected-(S4-NC_2-Pad5)") (class "Default")
      (node (ref "S4") (pin "5") (pinfunction "NC_2_5") (pintype "passive"))
    )
    (net (code "81") (name "unconnected-(S5-NC_2-Pad5)") (class "Default")
      (node (ref "S5") (pin "5") (pinfunction "NC_2_5") (pintype "passive"))
    )
    (net (code "82") (name "unconnected-(S5-NO_2-Pad3)") (class "Default")
      (node (ref "S5") (pin "3") (pinfunction "NO_2_3") (pintype "passive"))
    )
    (net (code "83") (name "unconnected-(S6-NC_2-Pad5)") (class "Default")
      (node (ref "S6") (pin "5") (pinfunction "NC_2_5") (pintype "passive"))
    )
    (net (code "84") (name "unconnected-(S6-NO_2-Pad3)") (class "Default")
      (node (ref "S6") (pin "3") (pinfunction "NO_2_3") (pintype "passive"))
    )
    (net (code "85") (name "unconnected-(S7-NC_2-Pad5)") (class "Default")
      (node (ref "S7") (pin "5") (pinfunction "NC_2_5") (pintype "passive"))
    )
    (net (code "86") (name "unconnected-(S8-NC_2-PadB1)") (class "Default")
      (node (ref "S8") (pin "B1") (pinfunction "NC_2_B1") (pintype "passive"))
    )
    (net (code "87") (name "unconnected-(S8-NO_1-PadA2)") (class "Default")
      (node (ref "S8") (pin "A2") (pinfunction "NO_1_A2") (pintype "passive"))
    )
    (net (code "88") (name "unconnected-(S9-NC_2-Pad5)") (class "Default")
      (node (ref "S9") (pin "5") (pinfunction "NC_2_5") (pintype "passive"))
    )
    (net (code "89") (name "unconnected-(S9-NO_2-Pad3)") (class "Default")
      (node (ref "S9") (pin "3") (pinfunction "NO_2_3") (pintype "passive"))
    )
    (net (code "90") (name "unconnected-(S10-NC_2-Pad5)") (class "Default")
      (node (ref "S10") (pin "5") (pinfunction "NC_2_5") (pintype "passive"))
    )
    (net (code "91") (name "unconnected-(S11-NC_2-Pad5)") (class "Default")
      (node (ref "S11") (pin "5") (pinfunction "NC_2_5") (pintype "passive"))
    )
    (net (code "92") (name "unconnected-(S11-NO_2-Pad3)") (class "Default")
      (node (ref "S11") (pin "3") (pinfunction "NO_2_3") (pintype "passive"))
    )
  )
)
